# I2c.net
KiCad netlist of a schematic drawn in Altium Designer
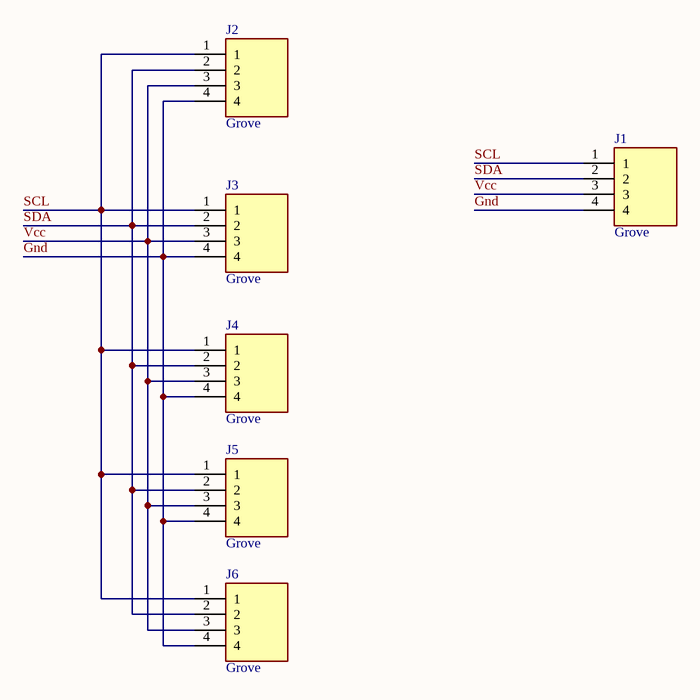
[diagram p0: I2c.SchDoc]

(export (version "E")
  (design (tool "Eeschema 10.0.6"))
  (components
    (comp (ref "J1")
      (value "Grove")
      (footprint "SEEED_110990030")
      (description "GROVE 2MM 4PIN VERT CONN 10PCS")
      (fields (field (name "MP") "110990030") (field (name "MF") "Seeed Technology"))
      (libsource (lib "110990030") (part "110990030"))
    )
    (comp (ref "J2")
      (value "Grove")
      (footprint "SEEED_110990030")
      (description "GROVE 2MM 4PIN VERT CONN 10PCS")
      (fields (field (name "MP") "110990030") (field (name "MF") "Seeed Technology"))
      (libsource (lib "110990030") (part "110990030"))
    )
    (comp (ref "J3")
      (value "Grove")
      (footprint "SEEED_110990030")
      (description "GROVE 2MM 4PIN VERT CONN 10PCS")
      (fields (field (name "MP") "110990030") (field (name "MF") "Seeed Technology"))
      (libsource (lib "110990030") (part "110990030"))
    )
    (comp (ref "J4")
      (value "Grove")
      (footprint "SEEED_110990030")
      (description "GROVE 2MM 4PIN VERT CONN 10PCS")
      (fields (field (name "MP") "110990030") (field (name "MF") "Seeed Technology"))
      (libsource (lib "110990030") (part "110990030"))
    )
    (comp (ref "J5")
      (value "Grove")
      (footprint "SEEED_110990030")
      (description "GROVE 2MM 4PIN VERT CONN 10PCS")
      (fields (field (name "MP") "110990030") (field (name "MF") "Seeed Technology"))
      (libsource (lib "110990030") (part "110990030"))
    )
    (comp (ref "J6")
      (value "Grove")
      (footprint "SEEED_110990030")
      (description "GROVE 2MM 4PIN VERT CONN 10PCS")
      (fields (field (name "MP") "110990030") (field (name "MF") "Seeed Technology"))
      (libsource (lib "110990030") (part "110990030"))
    )
  )
  (nets
    (net (code "1") (name "/Gnd") (class "Default")
      (node (ref "J1") (pin "4") (pinfunction "4_4") (pintype "passive"))
      (node (ref "J2") (pin "4") (pinfunction "4_4") (pintype "passive"))
      (node (ref "J3") (pin "4") (pinfunction "4_4") (pintype "passive"))
      (node (ref "J4") (pin "4") (pinfunction "4_4") (pintype "passive"))
      (node (ref "J5") (pin "4") (pinfunction "4_4") (pintype "passive"))
      (node (ref "J6") (pin "4") (pinfunction "4_4") (pintype "passive"))
    )
    (net (code "2") (name "/SCL") (class "Default")
      (node (ref "J1") (pin "1") (pinfunction "1_1") (pintype "passive"))
      (node (ref "J2") (pin "1") (pinfunction "1_1") (pintype "passive"))
      (node (ref "J3") (pin "1") (pinfunction "1_1") (pintype "passive"))
      (node (ref "J4") (pin "1") (pinfunction "1_1") (pintype "passive"))
      (node (ref "J5") (pin "1") (pinfunction "1_1") (pintype "passive"))
      (node (ref "J6") (pin "1") (pinfunction "1_1") (pintype "passive"))
    )
    (net (code "3") (name "/SDA") (class "Default")
      (node (ref "J1") (pin "2") (pinfunction "2_2") (pintype "passive"))
      (node (ref "J2") (pin "2") (pinfunction "2_2") (pintype "passive"))
      (node (ref "J3") (pin "2") (pinfunction "2_2") (pintype "passive"))
      (node (ref "J4") (pin "2") (pinfunction "2_2") (pintype "passive"))
      (node (ref "J5") (pin "2") (pinfunction "2_2") (pintype "passive"))
      (node (ref "J6") (pin "2") (pinfunction "2_2") (pintype "passive"))
    )
    (net (code "4") (name "/Vcc") (class "Default")
      (node (ref "J1") (pin "3") (pinfunction "3_3") (pintype "passive"))
      (node (ref "J2") (pin "3") (pinfunction "3_3") (pintype "passive"))
      (node (ref "J3") (pin "3") (pinfunction "3_3") (pintype "passive"))
      (node (ref "J4") (pin "3") (pinfunction "3_3") (pintype "passive"))
      (node (ref "J5") (pin "3") (pinfunction "3_3") (pintype "passive"))
      (node (ref "J6") (pin "3") (pinfunction "3_3") (pintype "passive"))
    )
  )
)
